# fabo-atmega-dev-au.net
KiCad netlist of a schematic drawn in EAGLE
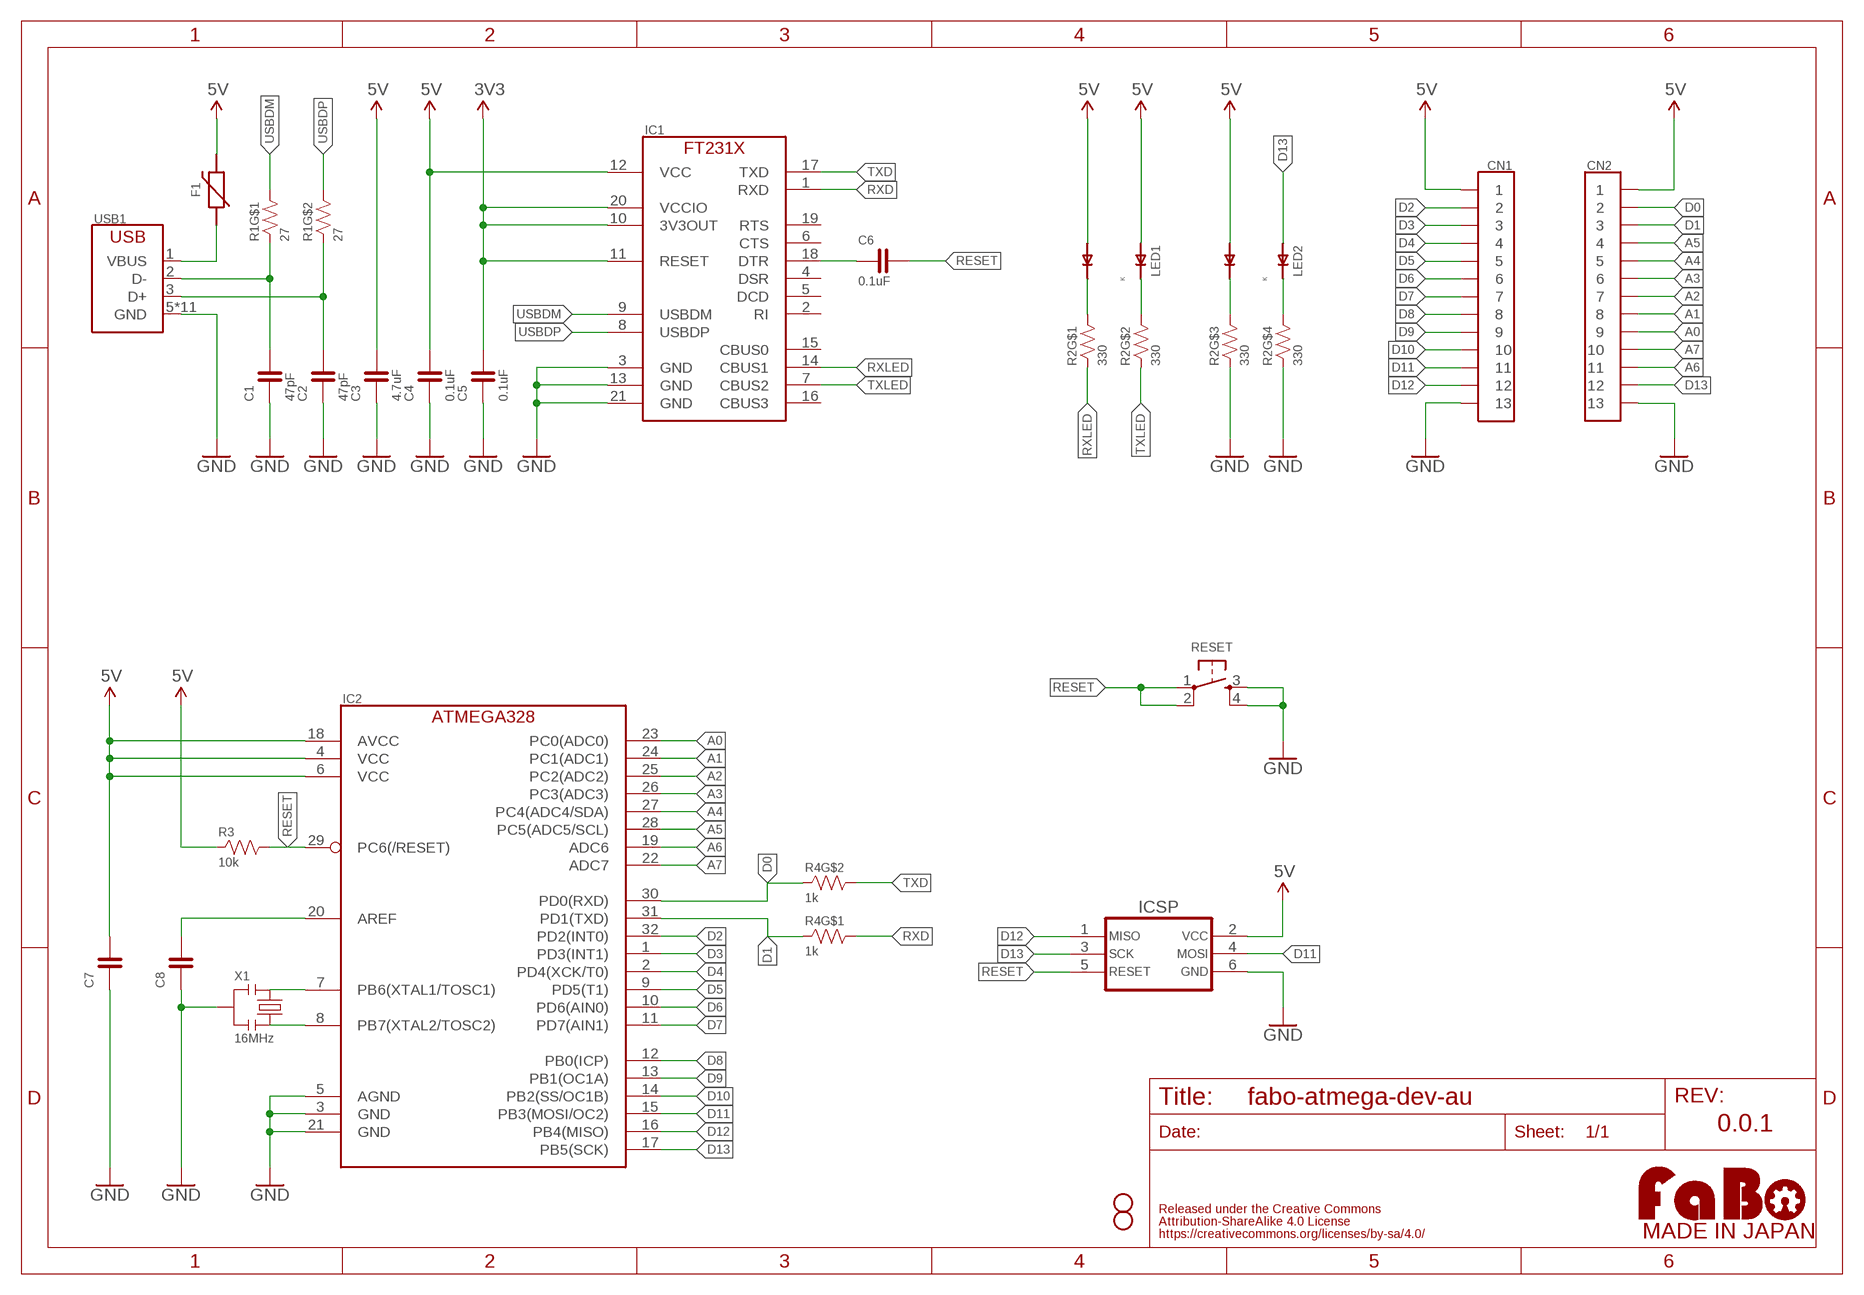
[diagram p0: schematic, sheet 1]

(export (version "E")
  (design (tool "Eeschema 10.0.6"))
  (components
    (comp (ref "C1")
      (value "47pF")
      (footprint "eagle-import:EIA0603")
      (libsource (lib "eagle-import") (part "CAPACITOR-0603"))
    )
    (comp (ref "C2")
      (value "47pF")
      (footprint "eagle-import:EIA0603")
      (libsource (lib "eagle-import") (part "CAPACITOR-0603"))
    )
    (comp (ref "C3")
      (value "4.7uF")
      (footprint "eagle-import:EIA0603")
      (libsource (lib "eagle-import") (part "CAPACITOR-0603"))
    )
    (comp (ref "C4")
      (value "0.1uF")
      (footprint "eagle-import:EIA0603")
      (libsource (lib "eagle-import") (part "CAPACITOR-0603"))
    )
    (comp (ref "C5")
      (value "0.1uF")
      (footprint "eagle-import:EIA0603")
      (libsource (lib "eagle-import") (part "CAPACITOR-0603"))
    )
    (comp (ref "C6")
      (value "0.1uF")
      (footprint "eagle-import:EIA0603")
      (libsource (lib "eagle-import") (part "CAPACITOR-0603"))
    )
    (comp (ref "C7")
      (value "CAPACITOR-0603")
      (footprint "eagle-import:EIA0603")
      (libsource (lib "eagle-import") (part "CAPACITOR-0603"))
    )
    (comp (ref "C8")
      (value "CAPACITOR-0603")
      (footprint "eagle-import:EIA0603")
      (libsource (lib "eagle-import") (part "CAPACITOR-0603"))
    )
    (comp (ref "CN1")
      (value "PIN_1X13_NARROW")
      (footprint "eagle-import:PIN_1X13_NARROW")
      (libsource (lib "eagle-import") (part "PIN_1X13_NARROW"))
    )
    (comp (ref "CN2")
      (value "PIN_1X13_NARROW")
      (footprint "eagle-import:PIN_1X13_NARROW")
      (libsource (lib "eagle-import") (part "PIN_1X13_NARROW"))
    )
    (comp (ref "F1")
      (value "PPTC-NANO")
      (footprint "eagle-import:NANOSMDC035F")
      (libsource (lib "eagle-import") (part "PPTC-NANO"))
    )
    (comp (ref "FID1")
      (value "FIDUCIAL-10")
      (footprint "eagle-import:FIDUCIAL_10")
      (libsource (lib "eagle-import") (part "FIDUCIAL-10"))
    )
    (comp (ref "FID2")
      (value "FIDUCIAL-10")
      (footprint "eagle-import:FIDUCIAL_10")
      (libsource (lib "eagle-import") (part "FIDUCIAL-10"))
    )
    (comp (ref "IC1")
      (value "FT231XQ")
      (footprint "eagle-import:QFN-20")
      (libsource (lib "eagle-import") (part "FT231XQ"))
    )
    (comp (ref "IC2")
      (value "ATMEGA328P-AU")
      (footprint "eagle-import:TQFP-32")
      (libsource (lib "eagle-import") (part "ATMEGA328P-AU"))
    )
    (comp (ref "ICSP")
      (value "ICSP_AVR-TC_NOHOLE")
      (footprint "eagle-import:TC2030")
      (libsource (lib "eagle-import") (part "ICSP_AVR-TC_NOHOLE"))
    )
    (comp (ref "LED1")
      (value "HSMF-C16X")
      (footprint "eagle-import:HSMF-C16X")
      (libsource (lib "eagle-import") (part "HSMF-C16X"))
    )
    (comp (ref "LED2")
      (value "HSMF-C16X")
      (footprint "eagle-import:HSMF-C16X")
      (libsource (lib "eagle-import") (part "HSMF-C16X"))
    )
    (comp (ref "LOGO1")
      (value "LOGO_FABO-M_BOTTOM")
      (footprint "eagle-import:LOGO_FABO_M_BOTTOM")
      (libsource (lib "eagle-import") (part "LOGO_FABO-M_BOTTOM"))
    )
    (comp (ref "R1")
      (value "27")
      (footprint "eagle-import:EXBV4V")
      (libsource (lib "eagle-import") (part "RESISTOR_ARRAY_2"))
    )
    (comp (ref "R2")
      (value "330")
      (footprint "eagle-import:EXBV8V")
      (libsource (lib "eagle-import") (part "RESISTOR_ARRAY_4"))
    )
    (comp (ref "R3")
      (value "10k")
      (footprint "eagle-import:EIA0603")
      (libsource (lib "eagle-import") (part "RESISTOR-0603"))
    )
    (comp (ref "R4")
      (value "1k")
      (footprint "eagle-import:EXBV4V")
      (libsource (lib "eagle-import") (part "RESISTOR_ARRAY_2"))
    )
    (comp (ref "RESET")
      (value "SWITCH-TACTILE-KMR2")
      (footprint "eagle-import:KMR2-TACT")
      (libsource (lib "eagle-import") (part "SWITCH-TACTILE-KMR2"))
    )
    (comp (ref "USB1")
      (value "USB-ZX62D")
      (footprint "eagle-import:ZX62D-B-5PA8")
      (libsource (lib "eagle-import") (part "USB-ZX62D"))
    )
    (comp (ref "X1")
      (value "16MHz")
      (footprint "eagle-import:CSTNE_V_C")
      (libsource (lib "eagle-import") (part "RESONATOR"))
    )
  )
  (nets
    (net (code "1") (name "3V3") (class "Default")
      (node (ref "C5") (pin "2") (pinfunction "2_2") (pintype "passive"))
      (node (ref "IC1") (pin "10") (pinfunction "3V3OUT_10") (pintype "bidirectional"))
      (node (ref "IC1") (pin "11") (pinfunction "RESET_11") (pintype "bidirectional"))
      (node (ref "IC1") (pin "20") (pinfunction "VCCIO_20") (pintype "bidirectional"))
    )
    (net (code "2") (name "5V") (class "Default")
      (node (ref "C3") (pin "2") (pinfunction "2_2") (pintype "passive"))
      (node (ref "C4") (pin "2") (pinfunction "2_2") (pintype "passive"))
      (node (ref "C7") (pin "2") (pinfunction "2_2") (pintype "passive"))
      (node (ref "CN1") (pin "1") (pinfunction "1_1") (pintype "bidirectional"))
      (node (ref "CN2") (pin "1") (pinfunction "1_1") (pintype "bidirectional"))
      (node (ref "F1") (pin "2") (pinfunction "2_2") (pintype "bidirectional"))
      (node (ref "IC1") (pin "12") (pinfunction "VCC_12") (pintype "bidirectional"))
      (node (ref "IC2") (pin "18") (pinfunction "AVCC_18") (pintype "bidirectional"))
      (node (ref "IC2") (pin "4") (pinfunction "VCC_4") (pintype "bidirectional"))
      (node (ref "IC2") (pin "6") (pinfunction "VCC_6") (pintype "bidirectional"))
      (node (ref "ICSP") (pin "2") (pinfunction "2_2") (pintype "passive"))
      (node (ref "LED1") (pin "1") (pinfunction "A1_1") (pintype "passive"))
      (node (ref "LED1") (pin "2") (pinfunction "A2_2") (pintype "bidirectional"))
      (node (ref "LED2") (pin "2") (pinfunction "A2_2") (pintype "bidirectional"))
      (node (ref "R3") (pin "1") (pinfunction "1_1") (pintype "bidirectional"))
    )
    (net (code "3") (name "A0") (class "Default")
      (node (ref "CN2") (pin "9") (pinfunction "9_9") (pintype "bidirectional"))
      (node (ref "IC2") (pin "23") (pinfunction "PC0(ADC0)_23") (pintype "bidirectional"))
    )
    (net (code "4") (name "A1") (class "Default")
      (node (ref "CN2") (pin "8") (pinfunction "8_8") (pintype "bidirectional"))
      (node (ref "IC2") (pin "24") (pinfunction "PC1(ADC1)_24") (pintype "bidirectional"))
    )
    (net (code "5") (name "A2") (class "Default")
      (node (ref "CN2") (pin "7") (pinfunction "7_7") (pintype "bidirectional"))
      (node (ref "IC2") (pin "25") (pinfunction "PC2(ADC2)_25") (pintype "bidirectional"))
    )
    (net (code "6") (name "A3") (class "Default")
      (node (ref "CN2") (pin "6") (pinfunction "6_6") (pintype "bidirectional"))
      (node (ref "IC2") (pin "26") (pinfunction "PC3(ADC3)_26") (pintype "bidirectional"))
    )
    (net (code "7") (name "A4") (class "Default")
      (node (ref "CN2") (pin "5") (pinfunction "5_5") (pintype "bidirectional"))
      (node (ref "IC2") (pin "27") (pinfunction "PC4(ADC4/SDA)_27") (pintype "bidirectional"))
    )
    (net (code "8") (name "A5") (class "Default")
      (node (ref "CN2") (pin "4") (pinfunction "4_4") (pintype "bidirectional"))
      (node (ref "IC2") (pin "28") (pinfunction "PC5(ADC5/SCL)_28") (pintype "bidirectional"))
    )
    (net (code "9") (name "A6") (class "Default")
      (node (ref "CN2") (pin "11") (pinfunction "11_11") (pintype "bidirectional"))
      (node (ref "IC2") (pin "19") (pinfunction "ADC6_19") (pintype "bidirectional"))
    )
    (net (code "10") (name "A7") (class "Default")
      (node (ref "CN2") (pin "10") (pinfunction "10_10") (pintype "bidirectional"))
      (node (ref "IC2") (pin "22") (pinfunction "ADC7_22") (pintype "bidirectional"))
    )
    (net (code "11") (name "D0") (class "Default")
      (node (ref "CN2") (pin "2") (pinfunction "2_2") (pintype "bidirectional"))
      (node (ref "IC2") (pin "30") (pinfunction "PD0(RXD)_30") (pintype "bidirectional"))
      (node (ref "R4") (pin "2") (pinfunction "1_2") (pintype "bidirectional"))
    )
    (net (code "12") (name "D1") (class "Default")
      (node (ref "CN2") (pin "3") (pinfunction "3_3") (pintype "bidirectional"))
      (node (ref "IC2") (pin "31") (pinfunction "PD1(TXD)_31") (pintype "bidirectional"))
      (node (ref "R4") (pin "1") (pinfunction "1_1") (pintype "bidirectional"))
    )
    (net (code "13") (name "D2") (class "Default")
      (node (ref "CN1") (pin "2") (pinfunction "2_2") (pintype "bidirectional"))
      (node (ref "IC2") (pin "32") (pinfunction "PD2(INT0)_32") (pintype "bidirectional"))
    )
    (net (code "14") (name "D3") (class "Default")
      (node (ref "CN1") (pin "3") (pinfunction "3_3") (pintype "bidirectional"))
      (node (ref "IC2") (pin "1") (pinfunction "PD3(INT1)_1") (pintype "bidirectional"))
    )
    (net (code "15") (name "D4") (class "Default")
      (node (ref "CN1") (pin "4") (pinfunction "4_4") (pintype "bidirectional"))
      (node (ref "IC2") (pin "2") (pinfunction "PD4(XCK/T0)_2") (pintype "bidirectional"))
    )
    (net (code "16") (name "D5") (class "Default")
      (node (ref "CN1") (pin "5") (pinfunction "5_5") (pintype "bidirectional"))
      (node (ref "IC2") (pin "9") (pinfunction "PD5(T1)_9") (pintype "bidirectional"))
    )
    (net (code "17") (name "D6") (class "Default")
      (node (ref "CN1") (pin "6") (pinfunction "6_6") (pintype "bidirectional"))
      (node (ref "IC2") (pin "10") (pinfunction "PD6(AIN0)_10") (pintype "bidirectional"))
    )
    (net (code "18") (name "D7") (class "Default")
      (node (ref "CN1") (pin "7") (pinfunction "7_7") (pintype "bidirectional"))
      (node (ref "IC2") (pin "11") (pinfunction "PD7(AIN1)_11") (pintype "bidirectional"))
    )
    (net (code "19") (name "D8") (class "Default")
      (node (ref "CN1") (pin "8") (pinfunction "8_8") (pintype "bidirectional"))
      (node (ref "IC2") (pin "12") (pinfunction "PB0(ICP)_12") (pintype "bidirectional"))
    )
    (net (code "20") (name "D9") (class "Default")
      (node (ref "CN1") (pin "9") (pinfunction "9_9") (pintype "bidirectional"))
      (node (ref "IC2") (pin "13") (pinfunction "PB1(OC1A)_13") (pintype "bidirectional"))
    )
    (net (code "21") (name "D10") (class "Default")
      (node (ref "CN1") (pin "10") (pinfunction "10_10") (pintype "bidirectional"))
      (node (ref "IC2") (pin "14") (pinfunction "PB2(SS/OC1B)_14") (pintype "bidirectional"))
    )
    (net (code "22") (name "D11") (class "Default")
      (node (ref "CN1") (pin "11") (pinfunction "11_11") (pintype "bidirectional"))
      (node (ref "IC2") (pin "15") (pinfunction "PB3(MOSI/OC2)_15") (pintype "bidirectional"))
      (node (ref "ICSP") (pin "4") (pinfunction "4_4") (pintype "passive"))
    )
    (net (code "23") (name "D12") (class "Default")
      (node (ref "CN1") (pin "12") (pinfunction "12_12") (pintype "bidirectional"))
      (node (ref "IC2") (pin "16") (pinfunction "PB4(MISO)_16") (pintype "bidirectional"))
      (node (ref "ICSP") (pin "1") (pinfunction "1_1") (pintype "passive"))
    )
    (net (code "24") (name "D13") (class "Default")
      (node (ref "CN2") (pin "12") (pinfunction "12_12") (pintype "bidirectional"))
      (node (ref "IC2") (pin "17") (pinfunction "PB5(SCK)_17") (pintype "bidirectional"))
      (node (ref "ICSP") (pin "3") (pinfunction "3_3") (pintype "passive"))
      (node (ref "LED2") (pin "1") (pinfunction "A1_1") (pintype "passive"))
    )
    (net (code "25") (name "GND") (class "Default")
      (node (ref "C1") (pin "1") (pinfunction "1_1") (pintype "passive"))
      (node (ref "C2") (pin "1") (pinfunction "1_1") (pintype "passive"))
      (node (ref "C3") (pin "1") (pinfunction "1_1") (pintype "passive"))
      (node (ref "C4") (pin "1") (pinfunction "1_1") (pintype "passive"))
      (node (ref "C5") (pin "1") (pinfunction "1_1") (pintype "passive"))
      (node (ref "C7") (pin "1") (pinfunction "1_1") (pintype "passive"))
      (node (ref "C8") (pin "1") (pinfunction "1_1") (pintype "passive"))
      (node (ref "CN1") (pin "13") (pinfunction "13_13") (pintype "bidirectional"))
      (node (ref "CN2") (pin "13") (pinfunction "13_13") (pintype "bidirectional"))
      (node (ref "IC1") (pin "13") (pinfunction "GND_13") (pintype "bidirectional"))
      (node (ref "IC1") (pin "21") (pinfunction "GND_21") (pintype "bidirectional"))
      (node (ref "IC1") (pin "3") (pinfunction "GND_3") (pintype "bidirectional"))
      (node (ref "IC2") (pin "21") (pinfunction "GND_21") (pintype "bidirectional"))
      (node (ref "IC2") (pin "3") (pinfunction "GND_3") (pintype "bidirectional"))
      (node (ref "IC2") (pin "5") (pinfunction "AGND_5") (pintype "bidirectional"))
      (node (ref "ICSP") (pin "6") (pinfunction "6_6") (pintype "passive"))
      (node (ref "R2") (pin "3") (pinfunction "1_3") (pintype "bidirectional"))
      (node (ref "R2") (pin "4") (pinfunction "1_4") (pintype "bidirectional"))
      (node (ref "RESET") (pin "3") (pinfunction "3_3") (pintype "passive"))
      (node (ref "RESET") (pin "4") (pinfunction "4_4") (pintype "passive"))
      (node (ref "USB1") (pin "5") (pinfunction "GND_5") (pintype "bidirectional"))
      (node (ref "USB1") (pin "B1") (pinfunction "GND_B1") (pintype "bidirectional"))
      (node (ref "USB1") (pin "B2") (pinfunction "GND_B2") (pintype "bidirectional"))
      (node (ref "USB1") (pin "B3") (pinfunction "GND_B3") (pintype "bidirectional"))
      (node (ref "USB1") (pin "B4") (pinfunction "GND_B4") (pintype "bidirectional"))
      (node (ref "USB1") (pin "T1") (pinfunction "GND_T1") (pintype "bidirectional"))
      (node (ref "USB1") (pin "T2") (pinfunction "GND_T2") (pintype "bidirectional"))
      (node (ref "USB1") (pin "T3") (pinfunction "GND_T3") (pintype "bidirectional"))
      (node (ref "USB1") (pin "T4") (pinfunction "GND_T4") (pintype "bidirectional"))
      (node (ref "USB1") (pin "T5") (pinfunction "GND_T5") (pintype "bidirectional"))
      (node (ref "USB1") (pin "T6") (pinfunction "GND_T6") (pintype "bidirectional"))
      (node (ref "X1") (pin "2") (pinfunction "2_2") (pintype "passive"))
    )
    (net (code "26") (name "Net-(IC1-DTR)") (class "Default")
      (node (ref "C6") (pin "1") (pinfunction "1_1") (pintype "passive"))
      (node (ref "IC1") (pin "18") (pinfunction "DTR_18") (pintype "bidirectional"))
    )
    (net (code "27") (name "Net-(IC2-AREF)") (class "Default")
      (node (ref "C8") (pin "2") (pinfunction "2_2") (pintype "passive"))
      (node (ref "IC2") (pin "20") (pinfunction "AREF_20") (pintype "bidirectional"))
    )
    (net (code "28") (name "Net-(IC2-PB6(XTAL1{slash}TOSC1))") (class "Default")
      (node (ref "IC2") (pin "7") (pinfunction "PB6(XTAL1/TOSC1)_7") (pintype "bidirectional"))
      (node (ref "X1") (pin "1") (pinfunction "1_1") (pintype "passive"))
    )
    (net (code "29") (name "Net-(IC2-PB7(XTAL2{slash}TOSC2))") (class "Default")
      (node (ref "IC2") (pin "8") (pinfunction "PB7(XTAL2/TOSC2)_8") (pintype "bidirectional"))
      (node (ref "X1") (pin "3") (pinfunction "3_3") (pintype "passive"))
    )
    (net (code "30") (name "Net-(LED1-K1)") (class "Default")
      (node (ref "LED1") (pin "3") (pinfunction "K1_3") (pintype "passive"))
      (node (ref "R2") (pin "7") (pinfunction "2_7") (pintype "bidirectional"))
    )
    (net (code "31") (name "Net-(LED1-K2)") (class "Default")
      (node (ref "LED1") (pin "4") (pinfunction "K2_4") (pintype "bidirectional"))
      (node (ref "R2") (pin "8") (pinfunction "2_8") (pintype "bidirectional"))
    )
    (net (code "32") (name "Net-(LED2-K1)") (class "Default")
      (node (ref "LED2") (pin "3") (pinfunction "K1_3") (pintype "passive"))
      (node (ref "R2") (pin "5") (pinfunction "2_5") (pintype "bidirectional"))
    )
    (net (code "33") (name "Net-(LED2-K2)") (class "Default")
      (node (ref "LED2") (pin "4") (pinfunction "K2_4") (pintype "bidirectional"))
      (node (ref "R2") (pin "6") (pinfunction "2_6") (pintype "bidirectional"))
    )
    (net (code "34") (name "Net-(R1B-1)") (class "Default")
      (node (ref "C2") (pin "2") (pinfunction "2_2") (pintype "passive"))
      (node (ref "R1") (pin "2") (pinfunction "1_2") (pintype "bidirectional"))
      (node (ref "USB1") (pin "3") (pinfunction "D+_3") (pintype "bidirectional"))
    )
    (net (code "35") (name "Net-(USB1-D-)") (class "Default")
      (node (ref "C1") (pin "2") (pinfunction "2_2") (pintype "passive"))
      (node (ref "R1") (pin "1") (pinfunction "1_1") (pintype "bidirectional"))
      (node (ref "USB1") (pin "2") (pinfunction "D-_2") (pintype "bidirectional"))
    )
    (net (code "36") (name "Net-(USB1-VBUS)") (class "Default")
      (node (ref "F1") (pin "1") (pinfunction "1_1") (pintype "bidirectional"))
      (node (ref "USB1") (pin "1") (pinfunction "VBUS_1") (pintype "bidirectional"))
    )
    (net (code "37") (name "RESET") (class "Default")
      (node (ref "C6") (pin "2") (pinfunction "2_2") (pintype "passive"))
      (node (ref "IC2") (pin "29") (pinfunction "PC6(/RESET)_29") (pintype "bidirectional"))
      (node (ref "ICSP") (pin "5") (pinfunction "5_5") (pintype "passive"))
      (node (ref "R3") (pin "2") (pinfunction "2_2") (pintype "bidirectional"))
      (node (ref "RESET") (pin "1") (pinfunction "1_1") (pintype "passive"))
      (node (ref "RESET") (pin "2") (pinfunction "2_2") (pintype "passive"))
    )
    (net (code "38") (name "RXD") (class "Default")
      (node (ref "IC1") (pin "1") (pinfunction "RXD_1") (pintype "bidirectional"))
      (node (ref "R4") (pin "4") (pinfunction "2_4") (pintype "bidirectional"))
    )
    (net (code "39") (name "RXLED") (class "Default")
      (node (ref "IC1") (pin "14") (pinfunction "CBUS1_14") (pintype "bidirectional"))
      (node (ref "R2") (pin "1") (pinfunction "1_1") (pintype "bidirectional"))
    )
    (net (code "40") (name "TXD") (class "Default")
      (node (ref "IC1") (pin "17") (pinfunction "TXD_17") (pintype "bidirectional"))
      (node (ref "R4") (pin "3") (pinfunction "2_3") (pintype "bidirectional"))
    )
    (net (code "41") (name "TXLED") (class "Default")
      (node (ref "IC1") (pin "7") (pinfunction "CBUS2_7") (pintype "bidirectional"))
      (node (ref "R2") (pin "2") (pinfunction "1_2") (pintype "bidirectional"))
    )
    (net (code "42") (name "USBDM") (class "Default")
      (node (ref "IC1") (pin "9") (pinfunction "USBDM_9") (pintype "bidirectional"))
      (node (ref "R1") (pin "4") (pinfunction "2_4") (pintype "bidirectional"))
    )
    (net (code "43") (name "USBDP") (class "Default")
      (node (ref "IC1") (pin "8") (pinfunction "USBDP_8") (pintype "bidirectional"))
      (node (ref "R1") (pin "3") (pinfunction "2_3") (pintype "bidirectional"))
    )
    (net (code "44") (name "unconnected-(IC1-CBUS0-Pad15)") (class "Default")
      (node (ref "IC1") (pin "15") (pinfunction "CBUS0_15") (pintype "bidirectional"))
    )
    (net (code "45") (name "unconnected-(IC1-CBUS3-Pad16)") (class "Default")
      (node (ref "IC1") (pin "16") (pinfunction "CBUS3_16") (pintype "bidirectional"))
    )
    (net (code "46") (name "unconnected-(IC1-CTS-Pad6)") (class "Default")
      (node (ref "IC1") (pin "6") (pinfunction "CTS_6") (pintype "bidirectional"))
    )
    (net (code "47") (name "unconnected-(IC1-DCD-Pad5)") (class "Default")
      (node (ref "IC1") (pin "5") (pinfunction "DCD_5") (pintype "bidirectional"))
    )
    (net (code "48") (name "unconnected-(IC1-DSR-Pad4)") (class "Default")
      (node (ref "IC1") (pin "4") (pinfunction "DSR_4") (pintype "bidirectional"))
    )
    (net (code "49") (name "unconnected-(IC1-RI-Pad2)") (class "Default")
      (node (ref "IC1") (pin "2") (pinfunction "RI_2") (pintype "bidirectional"))
    )
    (net (code "50") (name "unconnected-(IC1-RTS-Pad19)") (class "Default")
      (node (ref "IC1") (pin "19") (pinfunction "RTS_19") (pintype "bidirectional"))
    )
  )
)
